# Analog.net
KiCad netlist of a schematic drawn in Altium Designer
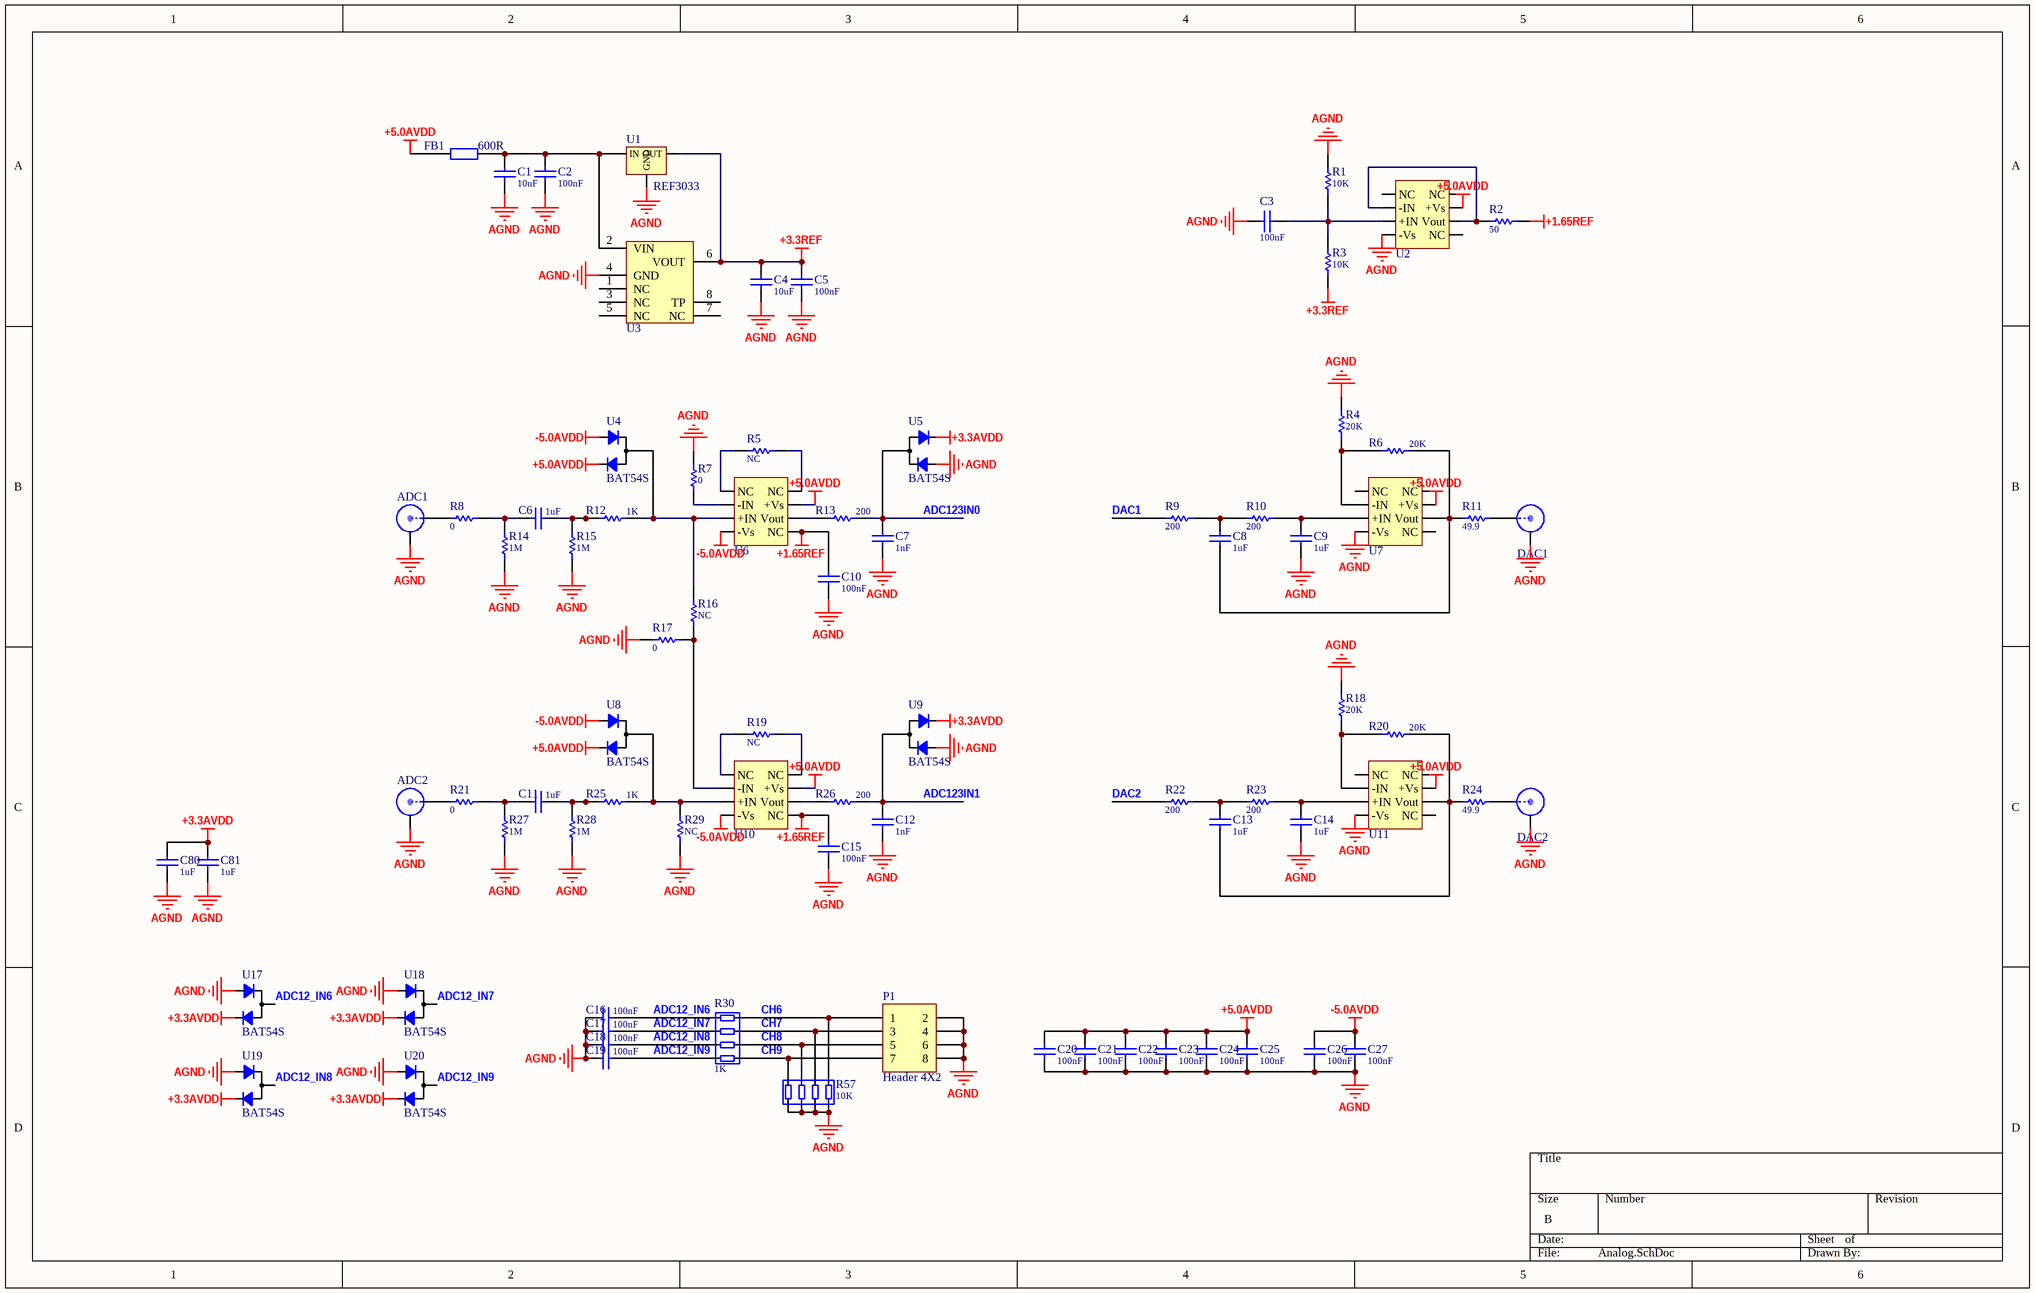
[diagram p0: Analog.SchDoc]

(export (version "E")
  (design (tool "Eeschema 10.0.6"))
  (components
    (comp (ref "ADC1") (value "SMA") (footprint "SMA_ANGLE") (libsource (lib "xz_C") (part "SMA")))
    (comp (ref "ADC2") (value "SMA") (footprint "SMA_ANGLE") (libsource (lib "xz_C") (part "SMA")))
    (comp (ref "C1")
      (value "10uF")
      (footprint "C0603-L")
      (description "贴片瓷片电容")
      (fields (field (name "Comment") "Cap-S"))
      (libsource (lib "xz_D") (part "Cap-S"))
    )
    (comp (ref "C2")
      (value "100nF")
      (footprint "C0603-L")
      (description "贴片瓷片电容")
      (fields (field (name "Comment") "Cap-S"))
      (libsource (lib "xz_D") (part "Cap-S"))
    )
    (comp (ref "C3")
      (value "100nF")
      (footprint "C0603-L")
      (description "贴片瓷片电容")
      (fields (field (name "Comment") "Cap-S"))
      (libsource (lib "xz_D") (part "Cap-S"))
    )
    (comp (ref "C4")
      (value "10uF")
      (footprint "C0603-L")
      (description "贴片瓷片电容")
      (fields (field (name "Comment") "Cap-S"))
      (libsource (lib "xz_D") (part "Cap-S"))
    )
    (comp (ref "C5")
      (value "100nF")
      (footprint "C0603-L")
      (description "贴片瓷片电容")
      (fields (field (name "Comment") "Cap-S"))
      (libsource (lib "xz_D") (part "Cap-S"))
    )
    (comp (ref "C6")
      (value "1uF")
      (footprint "C0603-L")
      (description "贴片瓷片电容")
      (fields (field (name "Comment") "Cap-S"))
      (libsource (lib "xz_D") (part "Cap-S"))
    )
    (comp (ref "C7")
      (value "1nF")
      (footprint "C0603-L")
      (description "贴片瓷片电容")
      (fields (field (name "Comment") "Cap-S"))
      (libsource (lib "xz_D") (part "Cap-S"))
    )
    (comp (ref "C8")
      (value "1uF")
      (footprint "C0603-L")
      (description "贴片瓷片电容")
      (fields (field (name "Comment") "Cap-S"))
      (libsource (lib "xz_D") (part "Cap-S"))
    )
    (comp (ref "C9")
      (value "1uF")
      (footprint "C0603-L")
      (description "贴片瓷片电容")
      (fields (field (name "Comment") "Cap-S"))
      (libsource (lib "xz_D") (part "Cap-S"))
    )
    (comp (ref "C10")
      (value "100nF")
      (footprint "C0603-L")
      (description "贴片瓷片电容")
      (fields (field (name "Comment") "Cap-S"))
      (libsource (lib "xz_D") (part "Cap-S"))
    )
    (comp (ref "C11")
      (value "1uF")
      (footprint "C0603-L")
      (description "贴片瓷片电容")
      (fields (field (name "Comment") "Cap-S"))
      (libsource (lib "xz_D") (part "Cap-S"))
    )
    (comp (ref "C12")
      (value "1nF")
      (footprint "C0603-L")
      (description "贴片瓷片电容")
      (fields (field (name "Comment") "Cap-S"))
      (libsource (lib "xz_D") (part "Cap-S"))
    )
    (comp (ref "C13")
      (value "1uF")
      (footprint "C0603-L")
      (description "贴片瓷片电容")
      (fields (field (name "Comment") "Cap-S"))
      (libsource (lib "xz_D") (part "Cap-S"))
    )
    (comp (ref "C14")
      (value "1uF")
      (footprint "C0603-L")
      (description "贴片瓷片电容")
      (fields (field (name "Comment") "Cap-S"))
      (libsource (lib "xz_D") (part "Cap-S"))
    )
    (comp (ref "C15")
      (value "100nF")
      (footprint "C0603-L")
      (description "贴片瓷片电容")
      (fields (field (name "Comment") "Cap-S"))
      (libsource (lib "xz_D") (part "Cap-S"))
    )
    (comp (ref "C16")
      (value "100nF")
      (footprint "C0603-L")
      (description "贴片瓷片电容")
      (fields (field (name "Comment") "Cap-S"))
      (libsource (lib "xz_D") (part "Cap-S"))
    )
    (comp (ref "C17")
      (value "100nF")
      (footprint "C0603-L")
      (description "贴片瓷片电容")
      (fields (field (name "Comment") "Cap-S"))
      (libsource (lib "xz_D") (part "Cap-S"))
    )
    (comp (ref "C18")
      (value "100nF")
      (footprint "C0603-L")
      (description "贴片瓷片电容")
      (fields (field (name "Comment") "Cap-S"))
      (libsource (lib "xz_D") (part "Cap-S"))
    )
    (comp (ref "C19")
      (value "100nF")
      (footprint "C0603-L")
      (description "贴片瓷片电容")
      (fields (field (name "Comment") "Cap-S"))
      (libsource (lib "xz_D") (part "Cap-S"))
    )
    (comp (ref "C20")
      (value "100nF")
      (footprint "C0603-L")
      (description "贴片瓷片电容")
      (fields (field (name "Comment") "Cap-S"))
      (libsource (lib "xz_D") (part "Cap-S"))
    )
    (comp (ref "C21")
      (value "100nF")
      (footprint "C0603-L")
      (description "贴片瓷片电容")
      (fields (field (name "Comment") "Cap-S"))
      (libsource (lib "xz_D") (part "Cap-S"))
    )
    (comp (ref "C22")
      (value "100nF")
      (footprint "C0603-L")
      (description "贴片瓷片电容")
      (fields (field (name "Comment") "Cap-S"))
      (libsource (lib "xz_D") (part "Cap-S"))
    )
    (comp (ref "C23")
      (value "100nF")
      (footprint "C0603-L")
      (description "贴片瓷片电容")
      (fields (field (name "Comment") "Cap-S"))
      (libsource (lib "xz_D") (part "Cap-S"))
    )
    (comp (ref "C24")
      (value "100nF")
      (footprint "C0603-L")
      (description "贴片瓷片电容")
      (fields (field (name "Comment") "Cap-S"))
      (libsource (lib "xz_D") (part "Cap-S"))
    )
    (comp (ref "C25")
      (value "100nF")
      (footprint "C0603-L")
      (description "贴片瓷片电容")
      (fields (field (name "Comment") "Cap-S"))
      (libsource (lib "xz_D") (part "Cap-S"))
    )
    (comp (ref "C26")
      (value "100nF")
      (footprint "C0603-L")
      (description "贴片瓷片电容")
      (fields (field (name "Comment") "Cap-S"))
      (libsource (lib "xz_D") (part "Cap-S"))
    )
    (comp (ref "C27")
      (value "100nF")
      (footprint "C0603-L")
      (description "贴片瓷片电容")
      (fields (field (name "Comment") "Cap-S"))
      (libsource (lib "xz_D") (part "Cap-S"))
    )
    (comp (ref "C80")
      (value "1uF")
      (footprint "C0603-L")
      (description "贴片瓷片电容")
      (fields (field (name "Comment") "Cap-S"))
      (libsource (lib "xz_D") (part "Cap-S"))
    )
    (comp (ref "C81")
      (value "1uF")
      (footprint "C0603-L")
      (description "贴片瓷片电容")
      (fields (field (name "Comment") "Cap-S"))
      (libsource (lib "xz_D") (part "Cap-S"))
    )
    (comp (ref "DAC1") (value "SMA") (footprint "SMA_ANGLE") (libsource (lib "xz_C") (part "SMA")))
    (comp (ref "DAC2") (value "SMA") (footprint "SMA_ANGLE") (libsource (lib "xz_C") (part "SMA")))
    (comp (ref "FB1") (value "600R") (footprint "FB-0805") (libsource (lib "CommonUsed") (part "FB")))
    (comp (ref "P1")
      (value "Header 4X2")
      (footprint "HDR2X4")
      (description "Header, 4-Pin, Dual row")
      (fields (field (name "PUBLISHER") "Altium Limited"))
      (libsource (lib "xz_C") (part "Header 4X2"))
    )
    (comp (ref "R1")
      (value "10K")
      (footprint "R0603-L")
      (description "贴片电阻")
      (fields (field (name "Comment") "R"))
      (libsource (lib "xz_D") (part "Res"))
    )
    (comp (ref "R2")
      (value "50")
      (footprint "R0603-L")
      (description "贴片电阻")
      (fields (field (name "Comment") "R"))
      (libsource (lib "xz_D") (part "Res"))
    )
    (comp (ref "R3")
      (value "10K")
      (footprint "R0603-L")
      (description "贴片电阻")
      (fields (field (name "Comment") "R"))
      (libsource (lib "xz_D") (part "Res"))
    )
    (comp (ref "R4")
      (value "20K")
      (footprint "R0603-L")
      (description "贴片电阻")
      (fields (field (name "Comment") "R"))
      (libsource (lib "xz_D") (part "Res"))
    )
    (comp (ref "R5")
      (value "NC")
      (footprint "R0603-L")
      (description "贴片电阻")
      (fields (field (name "Comment") "R"))
      (libsource (lib "xz_D") (part "Res"))
    )
    (comp (ref "R6")
      (value "20K")
      (footprint "R0603-L")
      (description "贴片电阻")
      (fields (field (name "Comment") "R"))
      (libsource (lib "xz_D") (part "Res"))
    )
    (comp (ref "R7")
      (value "0")
      (footprint "R0603-L")
      (description "贴片电阻")
      (fields (field (name "Comment") "R"))
      (libsource (lib "xz_D") (part "Res"))
    )
    (comp (ref "R8")
      (value "0")
      (footprint "R0603-L")
      (description "贴片电阻")
      (fields (field (name "Comment") "R"))
      (libsource (lib "xz_D") (part "Res"))
    )
    (comp (ref "R9")
      (value "200")
      (footprint "R0603-L")
      (description "贴片电阻")
      (fields (field (name "Comment") "R"))
      (libsource (lib "xz_D") (part "Res"))
    )
    (comp (ref "R10")
      (value "200")
      (footprint "R0603-L")
      (description "贴片电阻")
      (fields (field (name "Comment") "R"))
      (libsource (lib "xz_D") (part "Res"))
    )
    (comp (ref "R11")
      (value "49.9")
      (footprint "R0603-L")
      (description "贴片电阻")
      (fields (field (name "Comment") "R"))
      (libsource (lib "xz_D") (part "Res"))
    )
    (comp (ref "R12")
      (value "1K")
      (footprint "R0603-L")
      (description "贴片电阻")
      (fields (field (name "Comment") "R"))
      (libsource (lib "xz_D") (part "Res"))
    )
    (comp (ref "R13")
      (value "200")
      (footprint "R0603-L")
      (description "贴片电阻")
      (fields (field (name "Comment") "R"))
      (libsource (lib "xz_D") (part "Res"))
    )
    (comp (ref "R14")
      (value "1M")
      (footprint "R0603-L")
      (description "贴片电阻")
      (fields (field (name "Comment") "R"))
      (libsource (lib "xz_D") (part "Res"))
    )
    (comp (ref "R15")
      (value "1M")
      (footprint "R0603-L")
      (description "贴片电阻")
      (fields (field (name "Comment") "R"))
      (libsource (lib "xz_D") (part "Res"))
    )
    (comp (ref "R16")
      (value "NC")
      (footprint "R0603-L")
      (description "贴片电阻")
      (fields (field (name "Comment") "R"))
      (libsource (lib "xz_D") (part "Res"))
    )
    (comp (ref "R17")
      (value "0")
      (footprint "R0603-L")
      (description "贴片电阻")
      (fields (field (name "Comment") "R"))
      (libsource (lib "xz_D") (part "Res"))
    )
    (comp (ref "R18")
      (value "20K")
      (footprint "R0603-L")
      (description "贴片电阻")
      (fields (field (name "Comment") "R"))
      (libsource (lib "xz_D") (part "Res"))
    )
    (comp (ref "R19")
      (value "NC")
      (footprint "R0603-L")
      (description "贴片电阻")
      (fields (field (name "Comment") "R"))
      (libsource (lib "xz_D") (part "Res"))
    )
    (comp (ref "R20")
      (value "20K")
      (footprint "R0603-L")
      (description "贴片电阻")
      (fields (field (name "Comment") "R"))
      (libsource (lib "xz_D") (part "Res"))
    )
    (comp (ref "R21")
      (value "0")
      (footprint "R0603-L")
      (description "贴片电阻")
      (fields (field (name "Comment") "R"))
      (libsource (lib "xz_D") (part "Res"))
    )
    (comp (ref "R22")
      (value "200")
      (footprint "R0603-L")
      (description "贴片电阻")
      (fields (field (name "Comment") "R"))
      (libsource (lib "xz_D") (part "Res"))
    )
    (comp (ref "R23")
      (value "200")
      (footprint "R0603-L")
      (description "贴片电阻")
      (fields (field (name "Comment") "R"))
      (libsource (lib "xz_D") (part "Res"))
    )
    (comp (ref "R24")
      (value "49.9")
      (footprint "R0603-L")
      (description "贴片电阻")
      (fields (field (name "Comment") "R"))
      (libsource (lib "xz_D") (part "Res"))
    )
    (comp (ref "R25")
      (value "1K")
      (footprint "R0603-L")
      (description "贴片电阻")
      (fields (field (name "Comment") "R"))
      (libsource (lib "xz_D") (part "Res"))
    )
    (comp (ref "R26")
      (value "200")
      (footprint "R0603-L")
      (description "贴片电阻")
      (fields (field (name "Comment") "R"))
      (libsource (lib "xz_D") (part "Res"))
    )
    (comp (ref "R27")
      (value "1M")
      (footprint "R0603-L")
      (description "贴片电阻")
      (fields (field (name "Comment") "R"))
      (libsource (lib "xz_D") (part "Res"))
    )
    (comp (ref "R28")
      (value "1M")
      (footprint "R0603-L")
      (description "贴片电阻")
      (fields (field (name "Comment") "R"))
      (libsource (lib "xz_D") (part "Res"))
    )
    (comp (ref "R29")
      (value "NC")
      (footprint "R0603-L")
      (description "贴片电阻")
      (fields (field (name "Comment") "R"))
      (libsource (lib "xz_D") (part "Res"))
    )
    (comp (ref "R30")
      (value "1K")
      (footprint "R0603X4")
      (description "排阻 4")
      (fields (field (name "Comment") "R"))
      (libsource (lib "xz_D") (part "Res-4R"))
    )
    (comp (ref "R57")
      (value "10K")
      (footprint "R0603X4")
      (description "排阻 4")
      (fields (field (name "Comment") "R"))
      (libsource (lib "xz_D") (part "Res-4R"))
    )
    (comp (ref "U1")
      (value "REF3033")
      (footprint "SOT23-3_N")
      (description "采用 SOT23-3 封装的 2.5V 输出 50ppm/℃ 漂移 50uA 静态电流的（带隙）电压参考")
      (libsource (lib "xz_D") (part "REF3025"))
    )
    (comp (ref "U2")
      (value "OPA657")
      (footprint "SOIC-8_N")
      (description "1.6-GHz, Low-Noise, FET-Input Operational Amplifier")
      (fields (field (name "MANUFACTURER") "Texas Instruments") (field (name "PARTNUMBER") "OPA656U"))
      (libsource (lib "xz_D") (part "OPA657"))
    )
    (comp (ref "U3")
      (value "ADR45xx")
      (footprint "SOIC-8_N")
      (description "超低噪声、高精度  基准电压源")
      (libsource (lib "xz_D") (part "ADR45xx"))
    )
    (comp (ref "U4") (value "BAT54S") (footprint "SOT-23-3") (libsource (lib "CommonUsed") (part "BAT54S")))
    (comp (ref "U5") (value "BAT54S") (footprint "SOT-23-3") (libsource (lib "CommonUsed") (part "BAT54S")))
    (comp (ref "U6")
      (value "OPA657")
      (footprint "SOIC-8_N")
      (description "1.6-GHz, Low-Noise, FET-Input Operational Amplifier")
      (fields (field (name "MANUFACTURER") "Texas Instruments") (field (name "PARTNUMBER") "OPA656U"))
      (libsource (lib "xz_D") (part "OPA657"))
    )
    (comp (ref "U7")
      (value "OPA657")
      (footprint "SOIC-8_N")
      (description "1.6-GHz, Low-Noise, FET-Input Operational Amplifier")
      (fields (field (name "MANUFACTURER") "Texas Instruments") (field (name "PARTNUMBER") "OPA656U"))
      (libsource (lib "xz_D") (part "OPA657"))
    )
    (comp (ref "U8") (value "BAT54S") (footprint "SOT-23-3") (libsource (lib "CommonUsed") (part "BAT54S")))
    (comp (ref "U9") (value "BAT54S") (footprint "SOT-23-3") (libsource (lib "CommonUsed") (part "BAT54S")))
    (comp (ref "U10")
      (value "OPA657")
      (footprint "SOIC-8_N")
      (description "1.6-GHz, Low-Noise, FET-Input Operational Amplifier")
      (fields (field (name "MANUFACTURER") "Texas Instruments") (field (name "PARTNUMBER") "OPA656U"))
      (libsource (lib "xz_D") (part "OPA657"))
    )
    (comp (ref "U11")
      (value "OPA657")
      (footprint "SOIC-8_N")
      (description "1.6-GHz, Low-Noise, FET-Input Operational Amplifier")
      (fields (field (name "MANUFACTURER") "Texas Instruments") (field (name "PARTNUMBER") "OPA656U"))
      (libsource (lib "xz_D") (part "OPA657"))
    )
    (comp (ref "U17") (value "BAT54S") (footprint "SOT-23-3") (libsource (lib "CommonUsed") (part "BAT54S")))
    (comp (ref "U18") (value "BAT54S") (footprint "SOT-23-3") (libsource (lib "CommonUsed") (part "BAT54S")))
    (comp (ref "U19") (value "BAT54S") (footprint "SOT-23-3") (libsource (lib "CommonUsed") (part "BAT54S")))
    (comp (ref "U20") (value "BAT54S") (footprint "SOT-23-3") (libsource (lib "CommonUsed") (part "BAT54S")))
  )
  (nets
    (net (code "1") (name "+1.65REF") (class "Default")
      (node (ref "C10") (pin "1") (pinfunction "1_1") (pintype "passive"))
      (node (ref "C15") (pin "1") (pinfunction "1_1") (pintype "passive"))
      (node (ref "R2") (pin "1") (pinfunction "1_1") (pintype "passive"))
      (node (ref "U10") (pin "5") (pinfunction "NC_5") (pintype "passive"))
      (node (ref "U6") (pin "5") (pinfunction "NC_5") (pintype "passive"))
    )
    (net (code "2") (name "+3.3AVDD") (class "Default")
      (node (ref "C80") (pin "1") (pinfunction "1_1") (pintype "passive"))
      (node (ref "C81") (pin "1") (pinfunction "1_1") (pintype "passive"))
      (node (ref "U17") (pin "3") (pinfunction "3_3") (pintype "passive"))
      (node (ref "U18") (pin "3") (pinfunction "3_3") (pintype "passive"))
      (node (ref "U19") (pin "3") (pinfunction "3_3") (pintype "passive"))
      (node (ref "U20") (pin "3") (pinfunction "3_3") (pintype "passive"))
      (node (ref "U5") (pin "3") (pinfunction "3_3") (pintype "passive"))
      (node (ref "U9") (pin "3") (pinfunction "3_3") (pintype "passive"))
    )
    (net (code "3") (name "+3.3REF") (class "Default")
      (node (ref "C4") (pin "2") (pinfunction "2_2") (pintype "passive"))
      (node (ref "C5") (pin "2") (pinfunction "2_2") (pintype "passive"))
      (node (ref "R3") (pin "1") (pinfunction "1_1") (pintype "passive"))
      (node (ref "U1") (pin "2") (pinfunction "OUT_2") (pintype "passive"))
      (node (ref "U3") (pin "6") (pinfunction "VOUT_6") (pintype "passive"))
    )
    (net (code "4") (name "+5.0AVDD") (class "Default")
      (node (ref "C20") (pin "1") (pinfunction "1_1") (pintype "passive"))
      (node (ref "C21") (pin "1") (pinfunction "1_1") (pintype "passive"))
      (node (ref "C22") (pin "1") (pinfunction "1_1") (pintype "passive"))
      (node (ref "C23") (pin "1") (pinfunction "1_1") (pintype "passive"))
      (node (ref "C24") (pin "1") (pinfunction "1_1") (pintype "passive"))
      (node (ref "C25") (pin "1") (pinfunction "1_1") (pintype "passive"))
      (node (ref "FB1") (pin "1") (pinfunction "1_1") (pintype "passive"))
      (node (ref "U10") (pin "7") (pinfunction "+Vs_7") (pintype "passive"))
      (node (ref "U11") (pin "7") (pinfunction "+Vs_7") (pintype "passive"))
      (node (ref "U2") (pin "7") (pinfunction "+Vs_7") (pintype "passive"))
      (node (ref "U4") (pin "3") (pinfunction "3_3") (pintype "passive"))
      (node (ref "U6") (pin "7") (pinfunction "+Vs_7") (pintype "passive"))
      (node (ref "U7") (pin "7") (pinfunction "+Vs_7") (pintype "passive"))
      (node (ref "U8") (pin "3") (pinfunction "3_3") (pintype "passive"))
    )
    (net (code "5") (name "-5.0AVDD") (class "Default")
      (node (ref "C26") (pin "1") (pinfunction "1_1") (pintype "passive"))
      (node (ref "C27") (pin "1") (pinfunction "1_1") (pintype "passive"))
      (node (ref "U10") (pin "4") (pinfunction "-Vs_4") (pintype "passive"))
      (node (ref "U4") (pin "1") (pinfunction "1_1") (pintype "passive"))
      (node (ref "U6") (pin "4") (pinfunction "-Vs_4") (pintype "passive"))
      (node (ref "U8") (pin "1") (pinfunction "1_1") (pintype "passive"))
    )
    (net (code "6") (name "/ADC12_IN6") (class "Default")
      (node (ref "C16") (pin "1") (pinfunction "1_1") (pintype "passive"))
      (node (ref "R30") (pin "8") (pintype "passive"))
      (node (ref "U17") (pin "2") (pinfunction "2_2") (pintype "passive"))
    )
    (net (code "7") (name "/ADC12_IN7") (class "Default")
      (node (ref "C17") (pin "1") (pinfunction "1_1") (pintype "passive"))
      (node (ref "R30") (pin "7") (pintype "passive"))
      (node (ref "U18") (pin "2") (pinfunction "2_2") (pintype "passive"))
    )
    (net (code "8") (name "/ADC12_IN8") (class "Default")
      (node (ref "C18") (pin "1") (pinfunction "1_1") (pintype "passive"))
      (node (ref "R30") (pin "6") (pintype "passive"))
      (node (ref "U19") (pin "2") (pinfunction "2_2") (pintype "passive"))
    )
    (net (code "9") (name "/ADC12_IN9") (class "Default")
      (node (ref "C19") (pin "1") (pinfunction "1_1") (pintype "passive"))
      (node (ref "R30") (pin "5") (pintype "passive"))
      (node (ref "U20") (pin "2") (pinfunction "2_2") (pintype "passive"))
    )
    (net (code "10") (name "/ADC123IN0") (class "Default")
      (node (ref "C7") (pin "2") (pinfunction "2_2") (pintype "passive"))
      (node (ref "R13") (pin "2") (pinfunction "2_2") (pintype "passive"))
      (node (ref "U5") (pin "2") (pinfunction "2_2") (pintype "passive"))
    )
    (net (code "11") (name "/ADC123IN1") (class "Default")
      (node (ref "C12") (pin "2") (pinfunction "2_2") (pintype "passive"))
      (node (ref "R26") (pin "2") (pinfunction "2_2") (pintype "passive"))
      (node (ref "U9") (pin "2") (pinfunction "2_2") (pintype "passive"))
    )
    (net (code "12") (name "/CH6") (class "Default")
      (node (ref "P1") (pin "1") (pinfunction "1_1") (pintype "passive"))
      (node (ref "R30") (pin "1") (pintype "passive"))
      (node (ref "R57") (pin "4") (pintype "passive"))
    )
    (net (code "13") (name "/CH7") (class "Default")
      (node (ref "P1") (pin "3") (pinfunction "3_3") (pintype "passive"))
      (node (ref "R30") (pin "2") (pintype "passive"))
      (node (ref "R57") (pin "3") (pintype "passive"))
    )
    (net (code "14") (name "/CH8") (class "Default")
      (node (ref "P1") (pin "5") (pinfunction "5_5") (pintype "passive"))
      (node (ref "R30") (pin "3") (pintype "passive"))
      (node (ref "R57") (pin "2") (pintype "passive"))
    )
    (net (code "15") (name "/CH9") (class "Default")
      (node (ref "P1") (pin "7") (pinfunction "7_7") (pintype "passive"))
      (node (ref "R30") (pin "4") (pintype "passive"))
      (node (ref "R57") (pin "1") (pintype "passive"))
    )
    (net (code "16") (name "/DAC1") (class "Default")
      (node (ref "R9") (pin "2") (pinfunction "2_2") (pintype "passive"))
    )
    (net (code "17") (name "/DAC2") (class "Default")
      (node (ref "R22") (pin "2") (pinfunction "2_2") (pintype "passive"))
    )
    (net (code "18") (name "AGND") (class "Default")
      (node (ref "ADC1") (pin "2") (pinfunction "2_2") (pintype "passive"))
      (node (ref "ADC2") (pin "2") (pinfunction "2_2") (pintype "passive"))
      (node (ref "C1") (pin "1") (pinfunction "1_1") (pintype "passive"))
      (node (ref "C10") (pin "2") (pinfunction "2_2") (pintype "passive"))
      (node (ref "C12") (pin "1") (pinfunction "1_1") (pintype "passive"))
      (node (ref "C14") (pin "2") (pinfunction "2_2") (pintype "passive"))
      (node (ref "C15") (pin "2") (pinfunction "2_2") (pintype "passive"))
      (node (ref "C16") (pin "2") (pinfunction "2_2") (pintype "passive"))
      (node (ref "C17") (pin "2") (pinfunction "2_2") (pintype "passive"))
      (node (ref "C18") (pin "2") (pinfunction "2_2") (pintype "passive"))
      (node (ref "C19") (pin "2") (pinfunction "2_2") (pintype "passive"))
      (node (ref "C2") (pin "1") (pinfunction "1_1") (pintype "passive"))
      (node (ref "C20") (pin "2") (pinfunction "2_2") (pintype "passive"))
      (node (ref "C21") (pin "2") (pinfunction "2_2") (pintype "passive"))
      (node (ref "C22") (pin "2") (pinfunction "2_2") (pintype "passive"))
      (node (ref "C23") (pin "2") (pinfunction "2_2") (pintype "passive"))
      (node (ref "C24") (pin "2") (pinfunction "2_2") (pintype "passive"))
      (node (ref "C25") (pin "2") (pinfunction "2_2") (pintype "passive"))
      (node (ref "C26") (pin "2") (pinfunction "2_2") (pintype "passive"))
      (node (ref "C27") (pin "2") (pinfunction "2_2") (pintype "passive"))
      (node (ref "C3") (pin "2") (pinfunction "2_2") (pintype "passive"))
      (node (ref "C4") (pin "1") (pinfunction "1_1") (pintype "passive"))
      (node (ref "C5") (pin "1") (pinfunction "1_1") (pintype "passive"))
      (node (ref "C7") (pin "1") (pinfunction "1_1") (pintype "passive"))
      (node (ref "C80") (pin "2") (pinfunction "2_2") (pintype "passive"))
      (node (ref "C81") (pin "2") (pinfunction "2_2") (pintype "passive"))
      (node (ref "C9") (pin "2") (pinfunction "2_2") (pintype "passive"))
      (node (ref "DAC1") (pin "2") (pinfunction "2_2") (pintype "passive"))
      (node (ref "DAC2") (pin "2") (pinfunction "2_2") (pintype "passive"))
      (node (ref "P1") (pin "2") (pinfunction "2_2") (pintype "passive"))
      (node (ref "P1") (pin "4") (pinfunction "4_4") (pintype "passive"))
      (node (ref "P1") (pin "6") (pinfunction "6_6") (pintype "passive"))
      (node (ref "P1") (pin "8") (pinfunction "8_8") (pintype "passive"))
      (node (ref "R1") (pin "2") (pinfunction "2_2") (pintype "passive"))
      (node (ref "R14") (pin "1") (pinfunction "1_1") (pintype "passive"))
      (node (ref "R15") (pin "1") (pinfunction "1_1") (pintype "passive"))
      (node (ref "R17") (pin "2") (pinfunction "2_2") (pintype "passive"))
      (node (ref "R18") (pin "2") (pinfunction "2_2") (pintype "passive"))
      (node (ref "R27") (pin "1") (pinfunction "1_1") (pintype "passive"))
      (node (ref "R28") (pin "1") (pinfunction "1_1") (pintype "passive"))
      (node (ref "R29") (pin "2") (pinfunction "2_2") (pintype "passive"))
      (node (ref "R4") (pin "2") (pinfunction "2_2") (pintype "passive"))
      (node (ref "R57") (pin "5") (pintype "passive"))
      (node (ref "R57") (pin "6") (pintype "passive"))
      (node (ref "R57") (pin "7") (pintype "passive"))
      (node (ref "R57") (pin "8") (pintype "passive"))
      (node (ref "R7") (pin "2") (pinfunction "2_2") (pintype "passive"))
      (node (ref "U1") (pin "3") (pinfunction "GND_3") (pintype "passive"))
      (node (ref "U11") (pin "4") (pinfunction "-Vs_4") (pintype "passive"))
      (node (ref "U17") (pin "1") (pinfunction "1_1") (pintype "passive"))
      (node (ref "U18") (pin "1") (pinfunction "1_1") (pintype "passive"))
      (node (ref "U19") (pin "1") (pinfunction "1_1") (pintype "passive"))
      (node (ref "U2") (pin "4") (pinfunction "-Vs_4") (pintype "passive"))
      (node (ref "U20") (pin "1") (pinfunction "1_1") (pintype "passive"))
      (node (ref "U3") (pin "4") (pinfunction "GND_4") (pintype "passive"))
      (node (ref "U5") (pin "1") (pinfunction "1_1") (pintype "passive"))
      (node (ref "U7") (pin "4") (pinfunction "-Vs_4") (pintype "passive"))
      (node (ref "U9") (pin "1") (pinfunction "1_1") (pintype "passive"))
    )
    (net (code "19") (name "Net-(ADC1-Pad1)") (class "Default")
      (node (ref "ADC1") (pin "1") (pinfunction "1_1") (pintype "passive"))
      (node (ref "R8") (pin "2") (pinfunction "2_2") (pintype "passive"))
    )
    (net (code "20") (name "Net-(ADC2-Pad1)") (class "Default")
      (node (ref "ADC2") (pin "1") (pinfunction "1_1") (pintype "passive"))
      (node (ref "R21") (pin "2") (pinfunction "2_2") (pintype "passive"))
    )
    (net (code "21") (name "Net-(C6-Pad1)") (class "Default")
      (node (ref "C6") (pin "1") (pinfunction "1_1") (pintype "passive"))
      (node (ref "R12") (pin "1") (pinfunction "1_1") (pintype "passive"))
      (node (ref "R15") (pin "2") (pinfunction "2_2") (pintype "passive"))
    )
    (net (code "22") (name "Net-(C6-Pad2)") (class "Default")
      (node (ref "C6") (pin "2") (pinfunction "2_2") (pintype "passive"))
      (node (ref "R14") (pin "2") (pinfunction "2_2") (pintype "passive"))
      (node (ref "R8") (pin "1") (pinfunction "1_1") (pintype "passive"))
    )
    (net (code "23") (name "Net-(C8-Pad1)") (class "Default")
      (node (ref "C8") (pin "1") (pinfunction "1_1") (pintype "passive"))
      (node (ref "R10") (pin "2") (pinfunction "2_2") (pintype "passive"))
      (node (ref "R9") (pin "1") (pinfunction "1_1") (pintype "passive"))
    )
    (net (code "24") (name "Net-(C11-Pad1)") (class "Default")
      (node (ref "C11") (pin "1") (pinfunction "1_1") (pintype "passive"))
      (node (ref "R25") (pin "1") (pinfunction "1_1") (pintype "passive"))
      (node (ref "R28") (pin "2") (pinfunction "2_2") (pintype "passive"))
    )
    (net (code "25") (name "Net-(C11-Pad2)") (class "Default")
      (node (ref "C11") (pin "2") (pinfunction "2_2") (pintype "passive"))
      (node (ref "R21") (pin "1") (pinfunction "1_1") (pintype "passive"))
      (node (ref "R27") (pin "2") (pinfunction "2_2") (pintype "passive"))
    )
    (net (code "26") (name "Net-(C13-Pad1)") (class "Default")
      (node (ref "C13") (pin "1") (pinfunction "1_1") (pintype "passive"))
      (node (ref "R22") (pin "1") (pinfunction "1_1") (pintype "passive"))
      (node (ref "R23") (pin "2") (pinfunction "2_2") (pintype "passive"))
    )
    (net (code "27") (name "Net-(DAC1-Pad1)") (class "Default")
      (node (ref "DAC1") (pin "1") (pinfunction "1_1") (pintype "passive"))
      (node (ref "R11") (pin "1") (pinfunction "1_1") (pintype "passive"))
    )
    (net (code "28") (name "Net-(DAC2-Pad1)") (class "Default")
      (node (ref "DAC2") (pin "1") (pinfunction "1_1") (pintype "passive"))
      (node (ref "R24") (pin "1") (pinfunction "1_1") (pintype "passive"))
    )
    (net (code "29") (name "Net-(R5-Pad1)") (class "Default")
      (node (ref "R5") (pin "1") (pinfunction "1_1") (pintype "passive"))
      (node (ref "U6") (pin "8") (pinfunction "NC_8") (pintype "passive"))
    )
    (net (code "30") (name "Net-(R5-Pad2)") (class "Default")
      (node (ref "R5") (pin "2") (pinfunction "2_2") (pintype "passive"))
      (node (ref "U6") (pin "1") (pinfunction "NC_1") (pintype "passive"))
    )
    (net (code "31") (name "Net-(R19-Pad1)") (class "Default")
      (node (ref "R19") (pin "1") (pinfunction "1_1") (pintype "passive"))
      (node (ref "U10") (pin "8") (pinfunction "NC_8") (pintype "passive"))
    )
    (net (code "32") (name "Net-(R19-Pad2)") (class "Default")
      (node (ref "R19") (pin "2") (pinfunction "2_2") (pintype "passive"))
      (node (ref "U10") (pin "1") (pinfunction "NC_1") (pintype "passive"))
    )
    (net (code "33") (name "Net-(U1-IN)") (class "Default")
      (node (ref "C1") (pin "2") (pinfunction "2_2") (pintype "passive"))
      (node (ref "C2") (pin "2") (pinfunction "2_2") (pintype "passive"))
      (node (ref "FB1") (pin "2") (pinfunction "2_2") (pintype "passive"))
      (node (ref "U1") (pin "1") (pinfunction "IN_1") (pintype "passive"))
      (node (ref "U3") (pin "2") (pinfunction "VIN_2") (pintype "passive"))
    )
    (net (code "34") (name "Net-(U2-+IN)") (class "Default")
      (node (ref "C3") (pin "1") (pinfunction "1_1") (pintype "passive"))
      (node (ref "R1") (pin "1") (pinfunction "1_1") (pintype "passive"))
      (node (ref "R3") (pin "2") (pinfunction "2_2") (pintype "passive"))
      (node (ref "U2") (pin "3") (pinfunction "+IN_3") (pintype "passive"))
    )
    (net (code "35") (name "Net-(U2--IN)") (class "Default")
      (node (ref "R2") (pin "2") (pinfunction "2_2") (pintype "passive"))
      (node (ref "U2") (pin "2") (pinfunction "-IN_2") (pintype "passive"))
      (node (ref "U2") (pin "6") (pinfunction "Vout_6") (pintype "passive"))
    )
    (net (code "36") (name "Net-(U6-+IN)") (class "Default")
      (node (ref "R12") (pin "2") (pinfunction "2_2") (pintype "passive"))
      (node (ref "R16") (pin "2") (pinfunction "2_2") (pintype "passive"))
      (node (ref "U4") (pin "2") (pinfunction "2_2") (pintype "passive"))
      (node (ref "U6") (pin "3") (pinfunction "+IN_3") (pintype "passive"))
    )
    (net (code "37") (name "Net-(U6--IN)") (class "Default")
      (node (ref "R7") (pin "1") (pinfunction "1_1") (pintype "passive"))
      (node (ref "U6") (pin "2") (pinfunction "-IN_2") (pintype "passive"))
    )
    (net (code "38") (name "Net-(U6-Vout)") (class "Default")
      (node (ref "R13") (pin "1") (pinfunction "1_1") (pintype "passive"))
      (node (ref "U6") (pin "6") (pinfunction "Vout_6") (pintype "passive"))
    )
    (net (code "39") (name "Net-(U7-+IN)") (class "Default")
      (node (ref "C9") (pin "1") (pinfunction "1_1") (pintype "passive"))
      (node (ref "R10") (pin "1") (pinfunction "1_1") (pintype "passive"))
      (node (ref "U7") (pin "3") (pinfunction "+IN_3") (pintype "passive"))
    )
    (net (code "40") (name "Net-(U7--IN)") (class "Default")
      (node (ref "R4") (pin "1") (pinfunction "1_1") (pintype "passive"))
      (node (ref "R6") (pin "1") (pinfunction "1_1") (pintype "passive"))
      (node (ref "U7") (pin "2") (pinfunction "-IN_2") (pintype "passive"))
    )
    (net (code "41") (name "Net-(U7-Vout)") (class "Default")
      (node (ref "C8") (pin "2") (pinfunction "2_2") (pintype "passive"))
      (node (ref "R11") (pin "2") (pinfunction "2_2") (pintype "passive"))
      (node (ref "R6") (pin "2") (pinfunction "2_2") (pintype "passive"))
      (node (ref "U7") (pin "6") (pinfunction "Vout_6") (pintype "passive"))
    )
    (net (code "42") (name "Net-(U10-+IN)") (class "Default")
      (node (ref "R25") (pin "2") (pinfunction "2_2") (pintype "passive"))
      (node (ref "R29") (pin "1") (pinfunction "1_1") (pintype "passive"))
      (node (ref "U10") (pin "3") (pinfunction "+IN_3") (pintype "passive"))
      (node (ref "U8") (pin "2") (pinfunction "2_2") (pintype "passive"))
    )
    (net (code "43") (name "Net-(U10--IN)") (class "Default")
      (node (ref "R16") (pin "1") (pinfunction "1_1") (pintype "passive"))
      (node (ref "R17") (pin "1") (pinfunction "1_1") (pintype "passive"))
      (node (ref "U10") (pin "2") (pinfunction "-IN_2") (pintype "passive"))
    )
    (net (code "44") (name "Net-(U10-Vout)") (class "Default")
      (node (ref "R26") (pin "1") (pinfunction "1_1") (pintype "passive"))
      (node (ref "U10") (pin "6") (pinfunction "Vout_6") (pintype "passive"))
    )
    (net (code "45") (name "Net-(U11-+IN)") (class "Default")
      (node (ref "C14") (pin "1") (pinfunction "1_1") (pintype "passive"))
      (node (ref "R23") (pin "1") (pinfunction "1_1") (pintype "passive"))
      (node (ref "U11") (pin "3") (pinfunction "+IN_3") (pintype "passive"))
    )
    (net (code "46") (name "Net-(U11--IN)") (class "Default")
      (node (ref "R18") (pin "1") (pinfunction "1_1") (pintype "passive"))
      (node (ref "R20") (pin "1") (pinfunction "1_1") (pintype "passive"))
      (node (ref "U11") (pin "2") (pinfunction "-IN_2") (pintype "passive"))
    )
    (net (code "47") (name "Net-(U11-Vout)") (class "Default")
      (node (ref "C13") (pin "2") (pinfunction "2_2") (pintype "passive"))
      (node (ref "R20") (pin "2") (pinfunction "2_2") (pintype "passive"))
      (node (ref "R24") (pin "2") (pinfunction "2_2") (pintype "passive"))
      (node (ref "U11") (pin "6") (pinfunction "Vout_6") (pintype "passive"))
    )
    (net (code "48") (name "unconnected-(U2-NC-Pad1)") (class "Default")
      (node (ref "U2") (pin "1") (pinfunction "NC_1") (pintype "passive"))
    )
    (net (code "49") (name "unconnected-(U2-NC-Pad5)") (class "Default")
      (node (ref "U2") (pin "5") (pinfunction "NC_5") (pintype "passive"))
    )
    (net (code "50") (name "unconnected-(U2-NC-Pad8)") (class "Default")
      (node (ref "U2") (pin "8") (pinfunction "NC_8") (pintype "passive"))
    )
    (net (code "51") (name "unconnected-(U3-NC-Pad1)") (class "Default")
      (node (ref "U3") (pin "1") (pinfunction "NC_1") (pintype "passive"))
    )
    (net (code "52") (name "unconnected-(U3-NC-Pad3)") (class "Default")
      (node (ref "U3") (pin "3") (pinfunction "NC_3") (pintype "passive"))
    )
    (net (code "53") (name "unconnected-(U3-NC-Pad5)") (class "Default")
      (node (ref "U3") (pin "5") (pinfunction "NC_5") (pintype "passive"))
    )
    (net (code "54") (name "unconnected-(U3-NC-Pad7)") (class "Default")
      (node (ref "U3") (pin "7") (pinfunction "NC_7") (pintype "passive"))
    )
    (net (code "55") (name "unconnected-(U3-TP-Pad8)") (class "Default")
      (node (ref "U3") (pin "8") (pinfunction "TP_8") (pintype "passive"))
    )
    (net (code "56") (name "unconnected-(U7-NC-Pad1)") (class "Default")
      (node (ref "U7") (pin "1") (pinfunction "NC_1") (pintype "passive"))
    )
    (net (code "57") (name "unconnected-(U7-NC-Pad5)") (class "Default")
      (node (ref "U7") (pin "5") (pinfunction "NC_5") (pintype "passive"))
    )
    (net (code "58") (name "unconnected-(U7-NC-Pad8)") (class "Default")
      (node (ref "U7") (pin "8") (pinfunction "NC_8") (pintype "passive"))
    )
    (net (code "59") (name "unconnected-(U11-NC-Pad1)") (class "Default")
      (node (ref "U11") (pin "1") (pinfunction "NC_1") (pintype "passive"))
    )
    (net (code "60") (name "unconnected-(U11-NC-Pad5)") (class "Default")
      (node (ref "U11") (pin "5") (pinfunction "NC_5") (pintype "passive"))
    )
    (net (code "61") (name "unconnected-(U11-NC-Pad8)") (class "Default")
      (node (ref "U11") (pin "8") (pinfunction "NC_8") (pintype "passive"))
    )
  )
)
